# JTAG_Configuration.net
KiCad netlist of a schematic drawn in Altium Designer
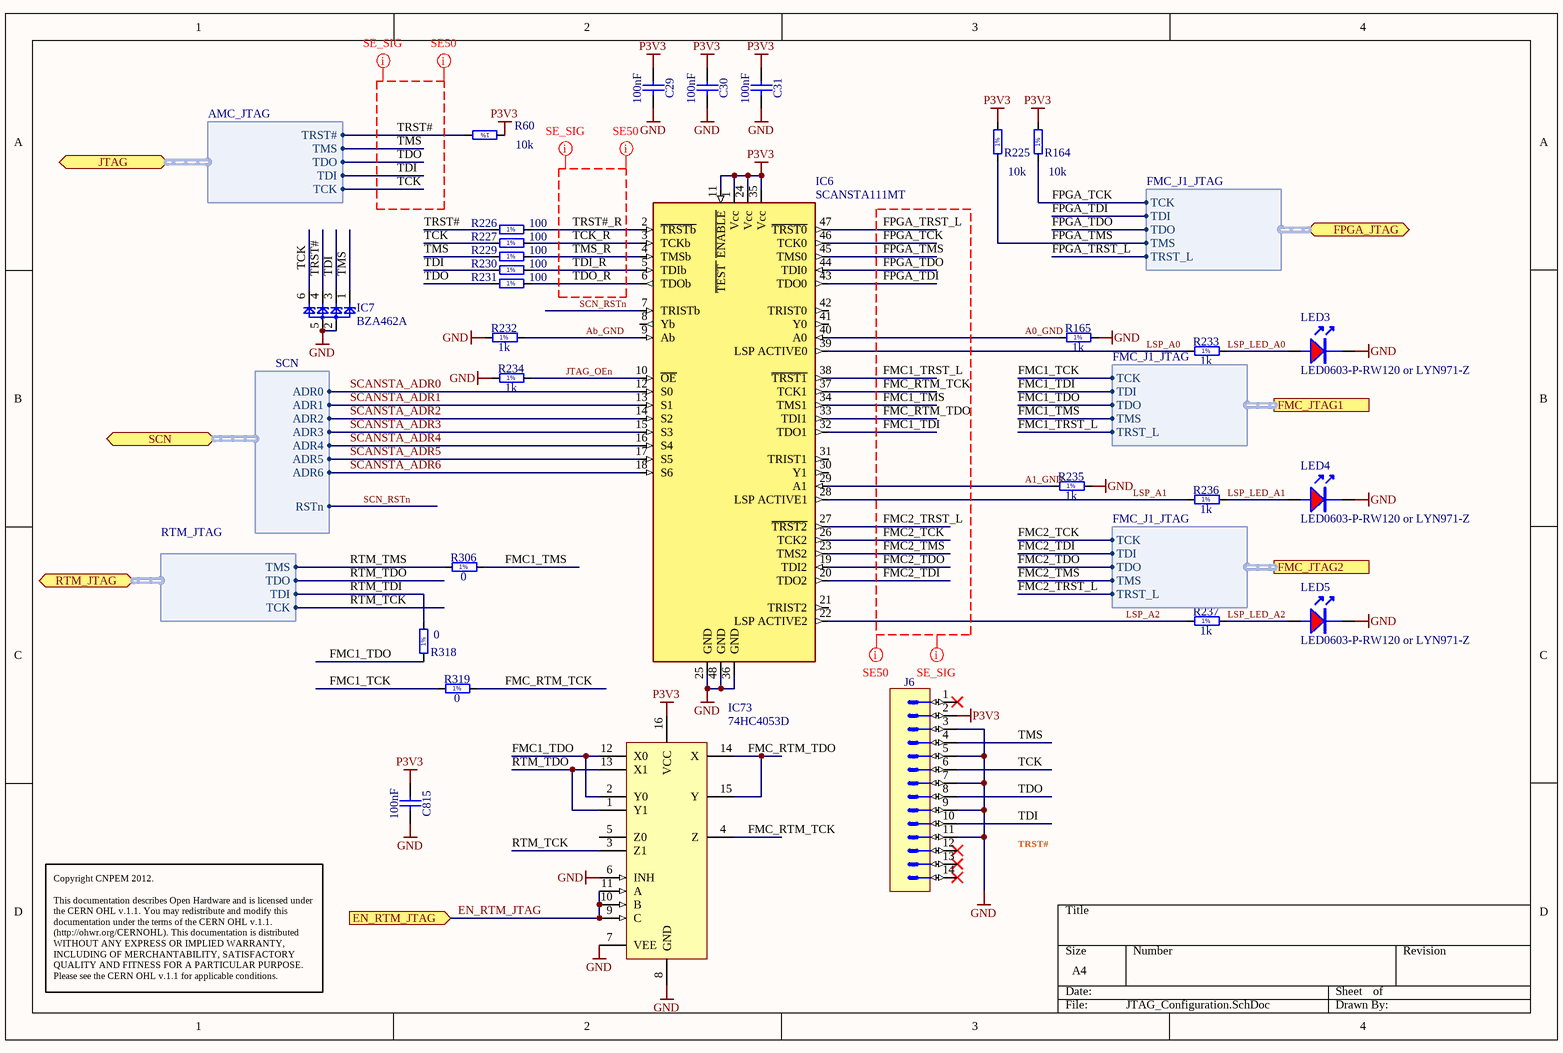
[diagram p0: JTAG_Configuration.SchDoc]

(export (version "E")
  (design (tool "Eeschema 10.0.6"))
  (components
    (comp (ref "C29")
      (value "100nF")
      (footprint "CAPC0603X33N")
      (description "Non-polarised capacitor")
      (fields
        (field (name "PART NUMBER") "CC0201_100NF_6.3V_10%_X5R")
        (field (name "VOLTAGE") "6.3V")
        (field (name "AUTHOR") "CERN DEM JLC")
      )
      (libsource (lib "Capacitors") (part "Capacitor - non polarized"))
    )
    (comp (ref "C30")
      (value "100nF")
      (footprint "CAPC0603X33N")
      (description "Non-polarised capacitor")
      (fields
        (field (name "PART NUMBER") "CC0201_100NF_6.3V_10%_X5R")
        (field (name "VOLTAGE") "6.3V")
        (field (name "AUTHOR") "CERN DEM JLC")
      )
      (libsource (lib "Capacitors") (part "Capacitor - non polarized"))
    )
    (comp (ref "C31")
      (value "100nF")
      (footprint "CAPC0603X33N")
      (description "Non-polarised capacitor")
      (fields
        (field (name "PART NUMBER") "CC0201_100NF_6.3V_10%_X5R")
        (field (name "VOLTAGE") "6.3V")
        (field (name "AUTHOR") "CERN DEM JLC")
      )
      (libsource (lib "Capacitors") (part "Capacitor - non polarized"))
    )
    (comp (ref "C815")
      (value "100nF")
      (footprint "CAPC0603X33N")
      (description "Non-polarised capacitor")
      (fields
        (field (name "PART NUMBER") "CC0201_100NF_6.3V_10%_X5R")
        (field (name "VOLTAGE") "6.3V")
        (field (name "AUTHOR") "CERN DEM JLC")
      )
      (libsource (lib "Capacitors") (part "Capacitor - non polarized"))
    )
    (comp (ref "IC6")
      (value "SCANSTA111MT")
      (footprint "TSSOP-48")
      (description "Enhanced SCAN Bridge Multidrop Addressable IEEE 1149.1 (JTAG) Port")
      (libsource (lib "LIBRARY_SCH") (part "IFC_SCANSTA111"))
    )
    (comp (ref "IC7")
      (value "BZA462A")
      (footprint "SOT23-6")
      (description "Quadruple 4V ESD transient voltage suppressor")
      (libsource (lib "LIBRARY_SCH") (part "D_TVS_BZA462A"))
    )
    (comp (ref "IC73") (value "74HC4053D") (footprint "SO-16") (libsource (lib "LIBRARY_SCH") (part "4053")))
    (comp (ref "J6")
      (value "Milli-Grid™")
      (footprint "MOLEX_87832-1420")
      (description "Connector 14 Male")
      (fields
        (field (name "PART NUMBER") "MOLEX_87832-1420")
        (field (name "MANUFACTURER") "MOLEX")
        (field (name "AUTHOR") "CERN DEM JLC")
      )
      (libsource (lib "Connectors") (part "Connector 14 Male"))
    )
    (comp (ref "LED3")
      (value "LED0603-P-RW120 or LYN971-Z")
      (footprint "led_0603R")
      (description "LED 0603 red")
      (libsource (lib "LIBRARY_SCH") (part "LED_0603R"))
    )
    (comp (ref "LED4")
      (value "LED0603-P-RW120 or LYN971-Z")
      (footprint "led_0603R")
      (description "LED 0603 red")
      (libsource (lib "LIBRARY_SCH") (part "LED_0603R"))
    )
    (comp (ref "LED5")
      (value "LED0603-P-RW120 or LYN971-Z")
      (footprint "led_0603R")
      (description "LED 0603 red")
      (libsource (lib "LIBRARY_SCH") (part "LED_0603R"))
    )
    (comp (ref "R60")
      (value "10k")
      (footprint "RESC1005X40N")
      (description "Resistor - 1%")
      (fields
        (field (name "PART NUMBER") "R0402_10K_1%_0.0625W_100PPM")
        (field (name "POWER") "0.0625W")
        (field (name "AUTHOR") "CERN DEM JLC")
      )
      (libsource (lib "Resistors") (part "Resistor - 1%"))
    )
    (comp (ref "R164")
      (value "10k")
      (footprint "RESC1005X40N")
      (description "Resistor - 1%")
      (fields
        (field (name "PART NUMBER") "R0402_10K_1%_0.0625W_100PPM")
        (field (name "POWER") "0.0625W")
        (field (name "AUTHOR") "CERN DEM JLC")
      )
      (libsource (lib "Resistors") (part "Resistor - 1%"))
    )
    (comp (ref "R165")
      (value "1k")
      (footprint "RESC1005X40N")
      (description "Resistor - 1%")
      (fields
        (field (name "PART NUMBER") "R0402_1K_1%_0.0625W_100PPM")
        (field (name "POWER") "0.0625W")
        (field (name "AUTHOR") "CERN DEM JLC")
      )
      (libsource (lib "Resistors") (part "Resistor - 1%"))
    )
    (comp (ref "R225")
      (value "10k")
      (footprint "RESC1005X40N")
      (description "Resistor - 1%")
      (fields
        (field (name "PART NUMBER") "R0402_10K_1%_0.0625W_100PPM")
        (field (name "POWER") "0.0625W")
        (field (name "AUTHOR") "CERN DEM JLC")
      )
      (libsource (lib "Resistors") (part "Resistor - 1%"))
    )
    (comp (ref "R226")
      (value "100")
      (footprint "RESC1005X40N")
      (description "Resistor - 1%")
      (fields
        (field (name "PART NUMBER") "R0402_100R_1%_0.0625W_100PPM")
        (field (name "POWER") "0.0625W")
        (field (name "AUTHOR") "CERN DEM JLC")
      )
      (libsource (lib "Resistors") (part "Resistor - 1%"))
    )
    (comp (ref "R227")
      (value "100")
      (footprint "RESC1005X40N")
      (description "Resistor - 1%")
      (fields
        (field (name "PART NUMBER") "R0402_100R_1%_0.0625W_100PPM")
        (field (name "POWER") "0.0625W")
        (field (name "AUTHOR") "CERN DEM JLC")
      )
      (libsource (lib "Resistors") (part "Resistor - 1%"))
    )
    (comp (ref "R229")
      (value "100")
      (footprint "RESC1005X40N")
      (description "Resistor - 1%")
      (fields
        (field (name "PART NUMBER") "R0402_100R_1%_0.0625W_100PPM")
        (field (name "POWER") "0.0625W")
        (field (name "AUTHOR") "CERN DEM JLC")
      )
      (libsource (lib "Resistors") (part "Resistor - 1%"))
    )
    (comp (ref "R230")
      (value "100")
      (footprint "RESC1005X40N")
      (description "Resistor - 1%")
      (fields
        (field (name "PART NUMBER") "R0402_100R_1%_0.0625W_100PPM")
        (field (name "POWER") "0.0625W")
        (field (name "AUTHOR") "CERN DEM JLC")
      )
      (libsource (lib "Resistors") (part "Resistor - 1%"))
    )
    (comp (ref "R231")
      (value "100")
      (footprint "RESC1005X40N")
      (description "Resistor - 1%")
      (fields
        (field (name "PART NUMBER") "R0402_100R_1%_0.0625W_100PPM")
        (field (name "POWER") "0.0625W")
        (field (name "AUTHOR") "CERN DEM JLC")
      )
      (libsource (lib "Resistors") (part "Resistor - 1%"))
    )
    (comp (ref "R232")
      (value "1k")
      (footprint "RESC1005X40N")
      (description "Resistor - 1%")
      (fields
        (field (name "PART NUMBER") "R0402_1K_1%_0.0625W_100PPM")
        (field (name "POWER") "0.0625W")
        (field (name "AUTHOR") "CERN DEM JLC")
      )
      (libsource (lib "Resistors") (part "Resistor - 1%"))
    )
    (comp (ref "R233")
      (value "1k")
      (footprint "RESC1005X40N")
      (description "Resistor - 1%")
      (fields
        (field (name "PART NUMBER") "R0402_1K_1%_0.0625W_100PPM")
        (field (name "POWER") "0.0625W")
        (field (name "AUTHOR") "CERN DEM JLC")
      )
      (libsource (lib "Resistors") (part "Resistor - 1%"))
    )
    (comp (ref "R234")
      (value "1k")
      (footprint "RESC1005X40N")
      (description "Resistor - 1%")
      (fields
        (field (name "PART NUMBER") "R0402_1K_1%_0.0625W_100PPM")
        (field (name "POWER") "0.0625W")
        (field (name "AUTHOR") "CERN DEM JLC")
      )
      (libsource (lib "Resistors") (part "Resistor - 1%"))
    )
    (comp (ref "R235")
      (value "1k")
      (footprint "RESC1005X40N")
      (description "Resistor - 1%")
      (fields
        (field (name "PART NUMBER") "R0402_1K_1%_0.0625W_100PPM")
        (field (name "POWER") "0.0625W")
        (field (name "AUTHOR") "CERN DEM JLC")
      )
      (libsource (lib "Resistors") (part "Resistor - 1%"))
    )
    (comp (ref "R236")
      (value "1k")
      (footprint "RESC1005X40N")
      (description "Resistor - 1%")
      (fields
        (field (name "PART NUMBER") "R0402_1K_1%_0.0625W_100PPM")
        (field (name "POWER") "0.0625W")
        (field (name "AUTHOR") "CERN DEM JLC")
      )
      (libsource (lib "Resistors") (part "Resistor - 1%"))
    )
    (comp (ref "R237")
      (value "1k")
      (footprint "RESC1005X40N")
      (description "Resistor - 1%")
      (fields
        (field (name "PART NUMBER") "R0402_1K_1%_0.0625W_100PPM")
        (field (name "POWER") "0.0625W")
        (field (name "AUTHOR") "CERN DEM JLC")
      )
      (libsource (lib "Resistors") (part "Resistor - 1%"))
    )
    (comp (ref "R306")
      (value "0")
      (footprint "RESC1005X40N")
      (description "Resistor - 1%")
      (fields
        (field (name "PART NUMBER") "R0402_0R_JUMPER")
        (field (name "MANUFACTURER") "GENERIC")
        (field (name "AUTHOR") "CERN DEM JLC")
      )
      (libsource (lib "Resistors") (part "Resistor - 1%"))
    )
    (comp (ref "R318")
      (value "0")
      (footprint "RESC1005X40N")
      (description "Resistor - 1%")
      (fields
        (field (name "PART NUMBER") "R0402_0R_JUMPER")
        (field (name "MANUFACTURER") "GENERIC")
        (field (name "AUTHOR") "CERN DEM JLC")
      )
      (libsource (lib "Resistors") (part "Resistor - 1%"))
    )
    (comp (ref "R319")
      (value "0")
      (footprint "RESC1005X40N")
      (description "Resistor - 1%")
      (fields
        (field (name "PART NUMBER") "R0402_0R_JUMPER")
        (field (name "MANUFACTURER") "GENERIC")
        (field (name "AUTHOR") "CERN DEM JLC")
      )
      (libsource (lib "Resistors") (part "Resistor - 1%"))
    )
  )
  (nets
    (net (code "5") (name "/A0_GND") (class "Default")
      (node (ref "IC6") (pin "40") (pinfunction "A0_40") (pintype "input"))
      (node (ref "R165") (pin "1") (pinfunction "1_1") (pintype "passive"))
    )
    (net (code "6") (name "/A1_GND") (class "Default")
      (node (ref "IC6") (pin "29") (pinfunction "A1_29") (pintype "input"))
      (node (ref "R235") (pin "1") (pinfunction "1_1") (pintype "passive"))
    )
    (net (code "7") (name "/Ab_GND") (class "Default")
      (node (ref "IC6") (pin "9") (pinfunction "Ab_9") (pintype "input"))
      (node (ref "R232") (pin "2") (pinfunction "2_2") (pintype "passive"))
    )
    (net (code "8") (name "/EN_RTM_JTAG") (class "Default")
      (node (ref "IC73") (pin "10") (pinfunction "B_10") (pintype "input"))
      (node (ref "IC73") (pin "11") (pinfunction "A_11") (pintype "input"))
      (node (ref "IC73") (pin "9") (pinfunction "C_9") (pintype "input"))
    )
    (net (code "9") (name "/FMC1_TCK") (class "Default")
      (node (ref "R319") (pin "1") (pinfunction "1_1") (pintype "passive"))
    )
    (net (code "10") (name "/FMC1_TDI") (class "Default")
      (node (ref "IC6") (pin "32") (pinfunction "TDO1_32") (pintype "output"))
    )
    (net (code "11") (name "/FMC1_TDO") (class "Default")
      (node (ref "IC73") (pin "12") (pinfunction "X0_12") (pintype "passive"))
      (node (ref "IC73") (pin "2") (pinfunction "Y0_2") (pintype "passive"))
      (node (ref "R318") (pin "1") (pinfunction "1_1") (pintype "passive"))
    )
    (net (code "12") (name "/FMC1_TMS") (class "Default")
      (node (ref "IC6") (pin "34") (pinfunction "TMS1_34") (pintype "output"))
      (node (ref "R306") (pin "2") (pinfunction "2_2") (pintype "passive"))
    )
    (net (code "13") (name "/FMC1_TRST_L") (class "Default")
      (node (ref "IC6") (pin "38") (pinfunction "~{TRST1}_38") (pintype "output"))
    )
    (net (code "14") (name "/FMC2_TCK") (class "Default")
      (node (ref "IC6") (pin "26") (pinfunction "TCK2_26") (pintype "output"))
    )
    (net (code "15") (name "/FMC2_TDI") (class "Default")
      (node (ref "IC6") (pin "20") (pinfunction "TDO2_20") (pintype "output"))
    )
    (net (code "16") (name "/FMC2_TDO") (class "Default")
      (node (ref "IC6") (pin "19") (pinfunction "TDI2_19") (pintype "input"))
    )
    (net (code "17") (name "/FMC2_TMS") (class "Default")
      (node (ref "IC6") (pin "23") (pinfunction "TMS2_23") (pintype "output"))
    )
    (net (code "18") (name "/FMC2_TRST_L") (class "Default")
      (node (ref "IC6") (pin "27") (pinfunction "~{TRST2}_27") (pintype "output"))
    )
    (net (code "19") (name "/FMC_RTM_TCK") (class "Default")
      (node (ref "IC6") (pin "37") (pinfunction "TCK1_37") (pintype "output"))
      (node (ref "IC73") (pin "4") (pinfunction "Z_4") (pintype "passive"))
      (node (ref "R319") (pin "2") (pinfunction "2_2") (pintype "passive"))
    )
    (net (code "20") (name "/FMC_RTM_TDO") (class "Default")
      (node (ref "IC6") (pin "33") (pinfunction "TDI1_33") (pintype "output"))
      (node (ref "IC73") (pin "14") (pinfunction "X_14") (pintype "passive"))
      (node (ref "IC73") (pin "15") (pinfunction "Y_15") (pintype "passive"))
    )
    (net (code "21") (name "/FPGA_TCK") (class "Default")
      (node (ref "IC6") (pin "46") (pinfunction "TCK0_46") (pintype "output"))
      (node (ref "R164") (pin "1") (pinfunction "1_1") (pintype "passive"))
    )
    (net (code "22") (name "/FPGA_TDI") (class "Default")
      (node (ref "IC6") (pin "43") (pinfunction "TDO0_43") (pintype "output"))
    )
    (net (code "23") (name "/FPGA_TDO") (class "Default")
      (node (ref "IC6") (pin "44") (pinfunction "TDI0_44") (pintype "input"))
    )
    (net (code "24") (name "/FPGA_TMS") (class "Default")
      (node (ref "IC6") (pin "45") (pinfunction "TMS0_45") (pintype "output"))
      (node (ref "R225") (pin "1") (pinfunction "1_1") (pintype "passive"))
    )
    (net (code "25") (name "/FPGA_TRST_L") (class "Default")
      (node (ref "IC6") (pin "47") (pinfunction "~{TRST0}_47") (pintype "output"))
    )
    (net (code "26") (name "/JTAG_OEn") (class "Default")
      (node (ref "IC6") (pin "10") (pinfunction "~{OE}_10") (pintype "input"))
      (node (ref "R234") (pin "2") (pinfunction "2_2") (pintype "passive"))
    )
    (net (code "27") (name "/LSP_A0") (class "Default")
      (node (ref "IC6") (pin "39") (pinfunction "LSP_ACTIVE0_39") (pintype "output"))
      (node (ref "R233") (pin "1") (pinfunction "1_1") (pintype "passive"))
    )
    (net (code "28") (name "/LSP_A1") (class "Default")
      (node (ref "IC6") (pin "28") (pinfunction "LSP_ACTIVE1_28") (pintype "output"))
      (node (ref "R236") (pin "1") (pinfunction "1_1") (pintype "passive"))
    )
    (net (code "29") (name "/LSP_A2") (class "Default")
      (node (ref "IC6") (pin "22") (pinfunction "LSP_ACTIVE2_22") (pintype "output"))
      (node (ref "R237") (pin "1") (pinfunction "1_1") (pintype "passive"))
    )
    (net (code "30") (name "/LSP_LED_A0") (class "Default")
      (node (ref "LED3") (pin "A") (pinfunction "A_A") (pintype "passive"))
      (node (ref "R233") (pin "2") (pinfunction "2_2") (pintype "passive"))
    )
    (net (code "31") (name "/LSP_LED_A1") (class "Default")
      (node (ref "LED4") (pin "A") (pinfunction "A_A") (pintype "passive"))
      (node (ref "R236") (pin "2") (pinfunction "2_2") (pintype "passive"))
    )
    (net (code "32") (name "/LSP_LED_A2") (class "Default")
      (node (ref "LED5") (pin "A") (pinfunction "A_A") (pintype "passive"))
      (node (ref "R237") (pin "2") (pinfunction "2_2") (pintype "passive"))
    )
    (net (code "33") (name "/RTM_TCK") (class "Default")
      (node (ref "IC73") (pin "3") (pinfunction "Z1_3") (pintype "passive"))
    )
    (net (code "34") (name "/RTM_TDI") (class "Default")
      (node (ref "R318") (pin "2") (pinfunction "2_2") (pintype "passive"))
    )
    (net (code "35") (name "/RTM_TDO") (class "Default")
      (node (ref "IC73") (pin "1") (pinfunction "Y1_1") (pintype "passive"))
      (node (ref "IC73") (pin "13") (pinfunction "X1_13") (pintype "passive"))
    )
    (net (code "36") (name "/RTM_TMS") (class "Default")
      (node (ref "R306") (pin "1") (pinfunction "1_1") (pintype "passive"))
    )
    (net (code "37") (name "/SCANSTA_ADR0") (class "Default")
      (node (ref "IC6") (pin "12") (pinfunction "S0_12") (pintype "input"))
    )
    (net (code "38") (name "/SCANSTA_ADR1") (class "Default")
      (node (ref "IC6") (pin "13") (pinfunction "S1_13") (pintype "input"))
    )
    (net (code "39") (name "/SCANSTA_ADR2") (class "Default")
      (node (ref "IC6") (pin "14") (pinfunction "S2_14") (pintype "input"))
    )
    (net (code "40") (name "/SCANSTA_ADR3") (class "Default")
      (node (ref "IC6") (pin "15") (pinfunction "S3_15") (pintype "input"))
    )
    (net (code "41") (name "/SCANSTA_ADR4") (class "Default")
      (node (ref "IC6") (pin "16") (pinfunction "S4_16") (pintype "input"))
    )
    (net (code "42") (name "/SCANSTA_ADR5") (class "Default")
      (node (ref "IC6") (pin "17") (pinfunction "S5_17") (pintype "input"))
    )
    (net (code "43") (name "/SCANSTA_ADR6") (class "Default")
      (node (ref "IC6") (pin "18") (pinfunction "S6_18") (pintype "input"))
    )
    (net (code "44") (name "/SCN_RSTn") (class "Default")
      (node (ref "IC6") (pin "7") (pinfunction "TRISTb_7") (pintype "input"))
    )
    (net (code "45") (name "/TCK") (class "Default")
      (node (ref "IC7") (pin "6") (pinfunction "6_6") (pintype "passive"))
      (node (ref "J6") (pin "6") (pinfunction "6_6") (pintype "bidirectional"))
      (node (ref "R227") (pin "1") (pinfunction "1_1") (pintype "passive"))
    )
    (net (code "46") (name "/TCK_R") (class "Default")
      (node (ref "IC6") (pin "3") (pinfunction "TCKb_3") (pintype "input"))
      (node (ref "R227") (pin "2") (pinfunction "2_2") (pintype "passive"))
    )
    (net (code "47") (name "/TDI") (class "Default")
      (node (ref "IC7") (pin "3") (pinfunction "3_3") (pintype "passive"))
      (node (ref "J6") (pin "10") (pinfunction "10_10") (pintype "bidirectional"))
      (node (ref "R230") (pin "1") (pinfunction "1_1") (pintype "passive"))
    )
    (net (code "48") (name "/TDI_R") (class "Default")
      (node (ref "IC6") (pin "5") (pinfunction "TDIb_5") (pintype "input"))
      (node (ref "R230") (pin "2") (pinfunction "2_2") (pintype "passive"))
    )
    (net (code "49") (name "/TDO") (class "Default")
      (node (ref "J6") (pin "8") (pinfunction "8_8") (pintype "bidirectional"))
      (node (ref "R231") (pin "1") (pinfunction "1_1") (pintype "passive"))
    )
    (net (code "50") (name "/TDO_R") (class "Default")
      (node (ref "IC6") (pin "6") (pinfunction "TDOb_6") (pintype "output"))
      (node (ref "R231") (pin "2") (pinfunction "2_2") (pintype "passive"))
    )
    (net (code "51") (name "/TMS") (class "Default")
      (node (ref "IC7") (pin "1") (pinfunction "1_1") (pintype "passive"))
      (node (ref "J6") (pin "4") (pinfunction "4_4") (pintype "bidirectional"))
      (node (ref "R229") (pin "1") (pinfunction "1_1") (pintype "passive"))
    )
    (net (code "52") (name "/TMS_R") (class "Default")
      (node (ref "IC6") (pin "4") (pinfunction "TMSb_4") (pintype "input"))
      (node (ref "R229") (pin "2") (pinfunction "2_2") (pintype "passive"))
    )
    (net (code "53") (name "/TRST#") (class "Default")
      (node (ref "IC7") (pin "4") (pinfunction "4_4") (pintype "passive"))
      (node (ref "R226") (pin "1") (pinfunction "1_1") (pintype "passive"))
      (node (ref "R60") (pin "2") (pinfunction "2_2") (pintype "passive"))
    )
    (net (code "54") (name "/TRST#_R") (class "Default")
      (node (ref "IC6") (pin "2") (pinfunction "~{TRSTb}_2") (pintype "input"))
      (node (ref "R226") (pin "2") (pinfunction "2_2") (pintype "passive"))
    )
    (net (code "59") (name "GND") (class "Default")
      (node (ref "C29") (pin "2") (pinfunction "2_2") (pintype "passive"))
      (node (ref "C30") (pin "2") (pinfunction "2_2") (pintype "passive"))
      (node (ref "C31") (pin "2") (pinfunction "2_2") (pintype "passive"))
      (node (ref "C815") (pin "2") (pinfunction "2_2") (pintype "passive"))
      (node (ref "IC6") (pin "25") (pinfunction "GND_25") (pintype "power_in"))
      (node (ref "IC6") (pin "36") (pinfunction "GND_36") (pintype "power_in"))
      (node (ref "IC6") (pin "48") (pinfunction "GND_48") (pintype "power_in"))
      (node (ref "IC7") (pin "2") (pinfunction "2_2") (pintype "passive"))
      (node (ref "IC7") (pin "5") (pinfunction "5_5") (pintype "passive"))
      (node (ref "IC73") (pin "6") (pinfunction "INH_6") (pintype "input"))
      (node (ref "IC73") (pin "7") (pinfunction "VEE_7") (pintype "passive"))
      (node (ref "IC73") (pin "8") (pinfunction "GND_8") (pintype "power_in"))
      (node (ref "J6") (pin "11") (pinfunction "11_11") (pintype "bidirectional"))
      (node (ref "J6") (pin "3") (pinfunction "3_3") (pintype "bidirectional"))
      (node (ref "J6") (pin "5") (pinfunction "5_5") (pintype "bidirectional"))
      (node (ref "J6") (pin "7") (pinfunction "7_7") (pintype "bidirectional"))
      (node (ref "J6") (pin "9") (pinfunction "9_9") (pintype "bidirectional"))
      (node (ref "LED3") (pin "K") (pinfunction "K_K") (pintype "passive"))
      (node (ref "LED4") (pin "K") (pinfunction "K_K") (pintype "passive"))
      (node (ref "LED5") (pin "K") (pinfunction "K_K") (pintype "passive"))
      (node (ref "R165") (pin "2") (pinfunction "2_2") (pintype "passive"))
      (node (ref "R232") (pin "1") (pinfunction "1_1") (pintype "passive"))
      (node (ref "R234") (pin "1") (pinfunction "1_1") (pintype "passive"))
      (node (ref "R235") (pin "2") (pinfunction "2_2") (pintype "passive"))
    )
    (net (code "60") (name "P3V3") (class "Default")
      (node (ref "C29") (pin "1") (pinfunction "1_1") (pintype "passive"))
      (node (ref "C30") (pin "1") (pinfunction "1_1") (pintype "passive"))
      (node (ref "C31") (pin "1") (pinfunction "1_1") (pintype "passive"))
      (node (ref "C815") (pin "1") (pinfunction "1_1") (pintype "passive"))
      (node (ref "IC6") (pin "1") (pinfunction "Vcc_1") (pintype "power_in"))
      (node (ref "IC6") (pin "11") (pinfunction "~{TEST_}_~{ENABLE}_11") (pintype "input"))
      (node (ref "IC6") (pin "24") (pinfunction "Vcc_24") (pintype "power_in"))
      (node (ref "IC6") (pin "35") (pinfunction "Vcc_35") (pintype "power_in"))
      (node (ref "IC73") (pin "16") (pinfunction "VCC_16") (pintype "power_in"))
      (node (ref "J6") (pin "2") (pinfunction "2_2") (pintype "bidirectional"))
      (node (ref "R164") (pin "2") (pinfunction "2_2") (pintype "passive"))
      (node (ref "R225") (pin "2") (pinfunction "2_2") (pintype "passive"))
      (node (ref "R60") (pin "1") (pinfunction "1_1") (pintype "passive"))
    )
    (net (code "61") (name "unconnected-(IC6-TRIST0-Pad42)") (class "Default")
      (node (ref "IC6") (pin "42") (pinfunction "TRIST0_42") (pintype "output"))
    )
    (net (code "62") (name "unconnected-(IC6-TRIST1-Pad31)") (class "Default")
      (node (ref "IC6") (pin "31") (pinfunction "TRIST1_31") (pintype "output"))
    )
    (net (code "63") (name "unconnected-(IC6-TRIST2-Pad21)") (class "Default")
      (node (ref "IC6") (pin "21") (pinfunction "TRIST2_21") (pintype "output"))
    )
    (net (code "64") (name "unconnected-(IC6-Y0-Pad41)") (class "Default")
      (node (ref "IC6") (pin "41") (pinfunction "Y0_41") (pintype "output"))
    )
    (net (code "65") (name "unconnected-(IC6-Y1-Pad30)") (class "Default")
      (node (ref "IC6") (pin "30") (pinfunction "Y1_30") (pintype "output"))
    )
    (net (code "66") (name "unconnected-(IC6-Yb-Pad8)") (class "Default")
      (node (ref "IC6") (pin "8") (pinfunction "Yb_8") (pintype "output"))
    )
    (net (code "67") (name "unconnected-(IC73-Z0-Pad5)") (class "Default")
      (node (ref "IC73") (pin "5") (pinfunction "Z0_5") (pintype "passive"))
    )
    (net (code "68") (name "unconnected-(J6-Pad1)") (class "Default")
      (node (ref "J6") (pin "1") (pinfunction "1_1") (pintype "bidirectional+no_connect"))
    )
    (net (code "69") (name "unconnected-(J6-Pad12)") (class "Default")
      (node (ref "J6") (pin "12") (pinfunction "12_12") (pintype "bidirectional+no_connect"))
    )
    (net (code "70") (name "unconnected-(J6-Pad13)") (class "Default")
      (node (ref "J6") (pin "13") (pinfunction "13_13") (pintype "bidirectional+no_connect"))
    )
    (net (code "71") (name "unconnected-(J6-Pad14)") (class "Default")
      (node (ref "J6") (pin "14") (pinfunction "14_14") (pintype "bidirectional+no_connect"))
    )
  )
)
